# 01_VS1053.net
KiCad netlist of a schematic drawn in Altium Designer
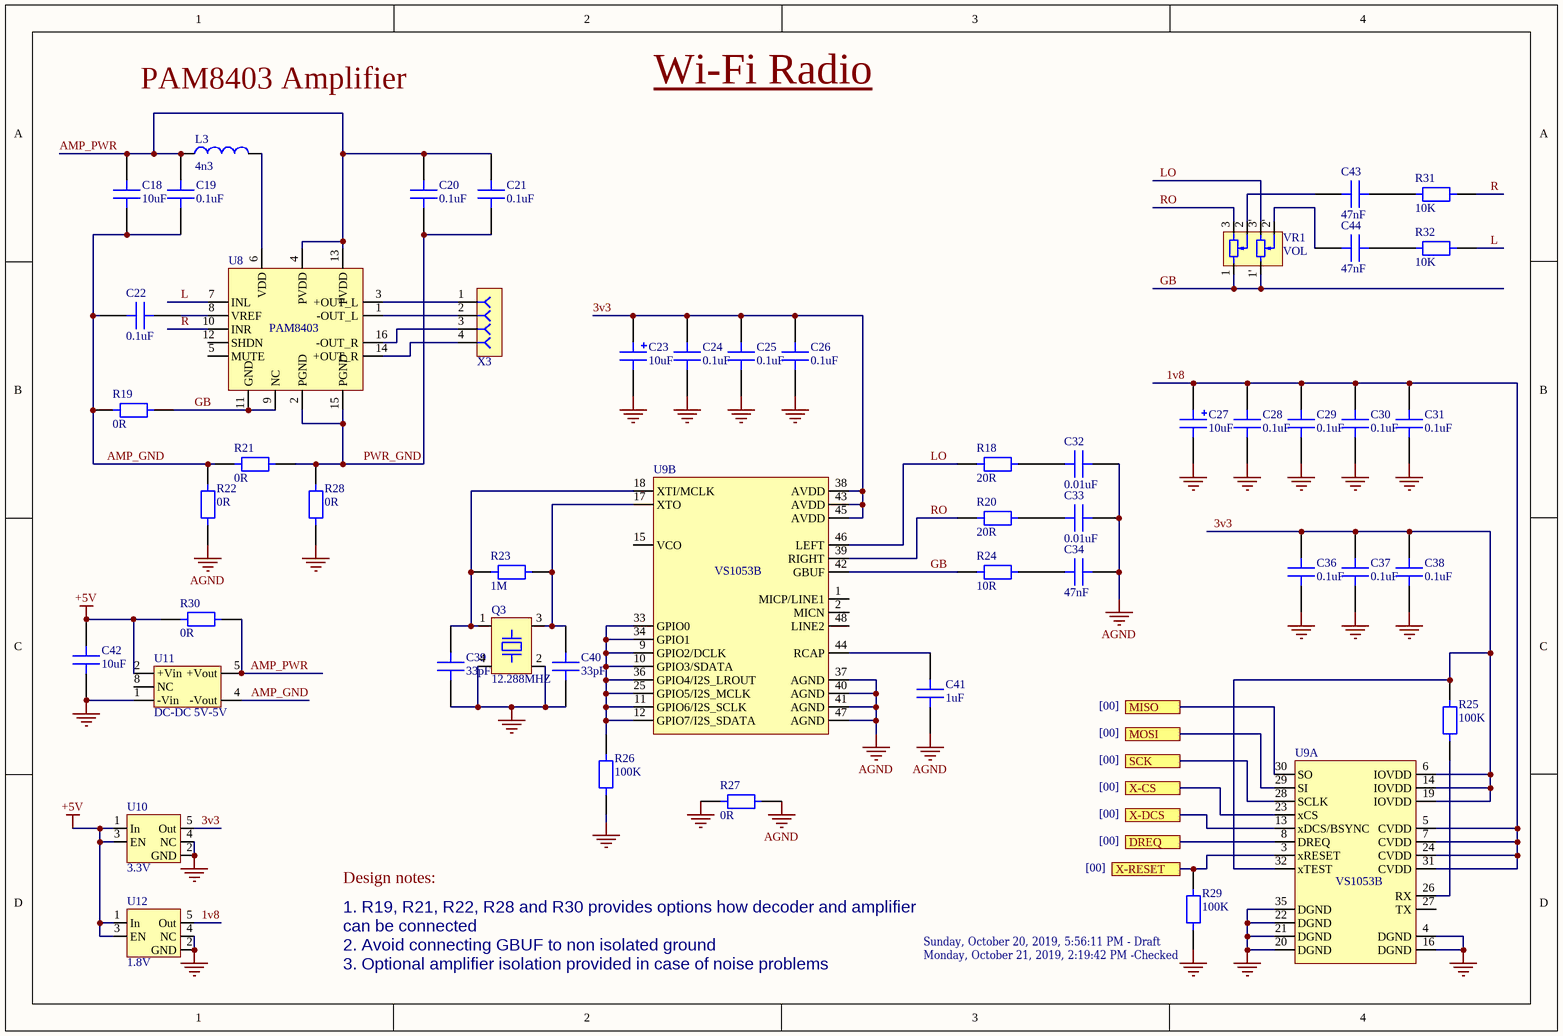
[diagram p0: [01] VS1053.SchDoc]

(export (version "E")
  (design (tool "Eeschema 10.0.6"))
  (components
    (comp (ref "C18")
      (value "10uF")
      (footprint "CAP 0603")
      (description "CAP CER 10UF 0603 6.3V")
      (fields
        (field (name "MANUFACTURER") "KEMET")
        (field (name "MANUFACTURER PART NUMBER") "C0603C106M9PACTU")
      )
      (libsource (lib "WiFi_Lib") (part "C0603C106M9PACTU"))
    )
    (comp (ref "C19")
      (value "0.1uF")
      (footprint "CAP 0603")
      (description "CAP CER 0.1uF 0603- SMD/SMT .1UF 25V 5% 0603")
      (fields
        (field (name "MANUFACTURER") "Vishay Vitramon")
        (field (name "MANUFACTURER PART NUMBER") "VJ0603Y104JXXAC")
      )
      (libsource (lib "WiFi_Lib") (part "VJ0603Y104JXXAC"))
    )
    (comp (ref "C20")
      (value "0.1uF")
      (footprint "CAP 0603")
      (description "CAP CER 0.1uF 0603- SMD/SMT .1UF 25V 5% 0603")
      (fields
        (field (name "MANUFACTURER") "Vishay Vitramon")
        (field (name "MANUFACTURER PART NUMBER") "VJ0603Y104JXXAC")
      )
      (libsource (lib "WiFi_Lib") (part "VJ0603Y104JXXAC"))
    )
    (comp (ref "C21")
      (value "0.1uF")
      (footprint "CAP 0603")
      (description "CAP CER 0.1uF 0603- SMD/SMT .1UF 25V 5% 0603")
      (fields
        (field (name "MANUFACTURER") "Vishay Vitramon")
        (field (name "MANUFACTURER PART NUMBER") "VJ0603Y104JXXAC")
      )
      (libsource (lib "WiFi_Lib") (part "VJ0603Y104JXXAC"))
    )
    (comp (ref "C22")
      (value "0.1uF")
      (footprint "CAP 0603")
      (description "CAP CER 0.1uF 0603- SMD/SMT .1UF 25V 5% 0603")
      (fields
        (field (name "MANUFACTURER") "Vishay Vitramon")
        (field (name "MANUFACTURER PART NUMBER") "VJ0603Y104JXXAC")
      )
      (libsource (lib "WiFi_Lib") (part "VJ0603Y104JXXAC"))
    )
    (comp (ref "C23")
      (value "10uF")
      (footprint "CAP 1206")
      (description "CAP TANT 10UF 1206 6.3V 10%")
      (fields
        (field (name "MANUFACTURER") "Vishay Sprague")
        (field (name "MANUFACTURER PART NUMBER") "293D106X96R3A2TE3")
      )
      (libsource (lib "WiFi_Lib") (part "293D106X96R3A2TE3"))
    )
    (comp (ref "C24")
      (value "0.1uF")
      (footprint "CAP 0603")
      (description "CAP CER 0.1uF 0603- SMD/SMT .1UF 25V 5% 0603")
      (fields
        (field (name "MANUFACTURER") "Vishay Vitramon")
        (field (name "MANUFACTURER PART NUMBER") "VJ0603Y104JXXAC")
      )
      (libsource (lib "WiFi_Lib") (part "VJ0603Y104JXXAC"))
    )
    (comp (ref "C25")
      (value "0.1uF")
      (footprint "CAP 0603")
      (description "CAP CER 0.1uF 0603- SMD/SMT .1UF 25V 5% 0603")
      (fields
        (field (name "MANUFACTURER") "Vishay Vitramon")
        (field (name "MANUFACTURER PART NUMBER") "VJ0603Y104JXXAC")
      )
      (libsource (lib "WiFi_Lib") (part "VJ0603Y104JXXAC"))
    )
    (comp (ref "C26")
      (value "0.1uF")
      (footprint "CAP 0603")
      (description "CAP CER 0.1uF 0603- SMD/SMT .1UF 25V 5% 0603")
      (fields
        (field (name "MANUFACTURER") "Vishay Vitramon")
        (field (name "MANUFACTURER PART NUMBER") "VJ0603Y104JXXAC")
      )
      (libsource (lib "WiFi_Lib") (part "VJ0603Y104JXXAC"))
    )
    (comp (ref "C27")
      (value "10uF")
      (footprint "CAP 1206")
      (description "CAP TANT 10UF 1206 6.3V 10%")
      (fields
        (field (name "MANUFACTURER") "Vishay Sprague")
        (field (name "MANUFACTURER PART NUMBER") "293D106X96R3A2TE3")
      )
      (libsource (lib "WiFi_Lib") (part "293D106X96R3A2TE3"))
    )
    (comp (ref "C28")
      (value "0.1uF")
      (footprint "CAP 0603")
      (description "CAP CER 0.1uF 0603- SMD/SMT .1UF 25V 5% 0603")
      (fields
        (field (name "MANUFACTURER") "Vishay Vitramon")
        (field (name "MANUFACTURER PART NUMBER") "VJ0603Y104JXXAC")
      )
      (libsource (lib "WiFi_Lib") (part "VJ0603Y104JXXAC"))
    )
    (comp (ref "C29")
      (value "0.1uF")
      (footprint "CAP 0603")
      (description "CAP CER 0.1uF 0603- SMD/SMT .1UF 25V 5% 0603")
      (fields
        (field (name "MANUFACTURER") "Vishay Vitramon")
        (field (name "MANUFACTURER PART NUMBER") "VJ0603Y104JXXAC")
      )
      (libsource (lib "WiFi_Lib") (part "VJ0603Y104JXXAC"))
    )
    (comp (ref "C30")
      (value "0.1uF")
      (footprint "CAP 0603")
      (description "CAP CER 0.1uF 0603- SMD/SMT .1UF 25V 5% 0603")
      (fields
        (field (name "MANUFACTURER") "Vishay Vitramon")
        (field (name "MANUFACTURER PART NUMBER") "VJ0603Y104JXXAC")
      )
      (libsource (lib "WiFi_Lib") (part "VJ0603Y104JXXAC"))
    )
    (comp (ref "C31")
      (value "0.1uF")
      (footprint "CAP 0603")
      (description "CAP CER 0.1uF 0603- SMD/SMT .1UF 25V 5% 0603")
      (fields
        (field (name "MANUFACTURER") "Vishay Vitramon")
        (field (name "MANUFACTURER PART NUMBER") "VJ0603Y104JXXAC")
      )
      (libsource (lib "WiFi_Lib") (part "VJ0603Y104JXXAC"))
    )
    (comp (ref "C32")
      (value "0.01uF")
      (footprint "CAP 0603")
      (description "CAP CER 0.01uF 0603 10 nF 50 V ±10 % Tolerance X7R SMT Multilayer Ceramic Chip Capacitor")
      (fields
        (field (name "MANUFACTURER") "Vishay Vitramon")
        (field (name "MANUFACTURER PART NUMBER") "VJ0603Y103KXAAC")
      )
      (libsource (lib "WiFi_Lib") (part "VJ0603Y103KXAAC"))
    )
    (comp (ref "C33")
      (value "0.01uF")
      (footprint "CAP 0603")
      (description "CAP CER 0.01uF 0603 10 nF 50 V ±10 % Tolerance X7R SMT Multilayer Ceramic Chip Capacitor")
      (fields
        (field (name "MANUFACTURER") "Vishay Vitramon")
        (field (name "MANUFACTURER PART NUMBER") "VJ0603Y103KXAAC")
      )
      (libsource (lib "WiFi_Lib") (part "VJ0603Y103KXAAC"))
    )
    (comp (ref "C34")
      (value "47nF")
      (footprint "CAP 0603")
      (description "CAP CER 47nF 0603 25 V ±5 % Tolerance X7R SMT Multilayer Ceramic Chip Capacitor")
      (fields
        (field (name "MANUFACTURER") "Vishay Vitramon")
        (field (name "MANUFACTURER PART NUMBER") "VJ0603Y473JXXCW1BC")
      )
      (libsource (lib "WiFi_Lib") (part "VJ0603Y473JXXCW1BC"))
    )
    (comp (ref "C36")
      (value "0.1uF")
      (footprint "CAP 0603")
      (description "CAP CER 0.1uF 0603- SMD/SMT .1UF 25V 5% 0603")
      (fields
        (field (name "MANUFACTURER") "Vishay Vitramon")
        (field (name "MANUFACTURER PART NUMBER") "VJ0603Y104JXXAC")
      )
      (libsource (lib "WiFi_Lib") (part "VJ0603Y104JXXAC"))
    )
    (comp (ref "C37")
      (value "0.1uF")
      (footprint "CAP 0603")
      (description "CAP CER 0.1uF 0603- SMD/SMT .1UF 25V 5% 0603")
      (fields
        (field (name "MANUFACTURER") "Vishay Vitramon")
        (field (name "MANUFACTURER PART NUMBER") "VJ0603Y104JXXAC")
      )
      (libsource (lib "WiFi_Lib") (part "VJ0603Y104JXXAC"))
    )
    (comp (ref "C38")
      (value "0.1uF")
      (footprint "CAP 0603")
      (description "CAP CER 0.1uF 0603- SMD/SMT .1UF 25V 5% 0603")
      (fields
        (field (name "MANUFACTURER") "Vishay Vitramon")
        (field (name "MANUFACTURER PART NUMBER") "VJ0603Y104JXXAC")
      )
      (libsource (lib "WiFi_Lib") (part "VJ0603Y104JXXAC"))
    )
    (comp (ref "C39")
      (value "33pF")
      (footprint "CAP 0603")
      (description "CAP CER 33PF 0603 250V C0G/NP0")
      (fields
        (field (name "MANUFACTURER") "Johanson")
        (field (name "MANUFACTURER PART NUMBER") "251R14S330GV4T")
      )
      (libsource (lib "WiFi_Lib") (part "251R14S330GV4T"))
    )
    (comp (ref "C40")
      (value "33pF")
      (footprint "CAP 0603")
      (description "CAP CER 33PF 0603 250V C0G/NP0")
      (fields
        (field (name "MANUFACTURER") "Johanson")
        (field (name "MANUFACTURER PART NUMBER") "251R14S330GV4T")
      )
      (libsource (lib "WiFi_Lib") (part "251R14S330GV4T"))
    )
    (comp (ref "C41")
      (value "1uF")
      (footprint "CAP 0603")
      (description "CAP CER 1uF 0603 16V X7R 10% SMD 125C Paper T/R")
      (fields
        (field (name "MANUFACTURER") "Vishay Semiconductors")
        (field (name "MANUFACTURER PART NUMBER") "VJ0603Y105KXJCW1BC")
      )
      (libsource (lib "WiFi_Lib") (part "VJ0603Y105KXJCW1BC"))
    )
    (comp (ref "C42")
      (value "10uF")
      (footprint "CAP 0805")
      (description "CAP CER 10UF 0805 10V X5R")
      (fields
        (field (name "MANUFACTURER") "KEMET")
        (field (name "MANUFACTURER PART NUMBER") "C0805C106K8PACTU")
      )
      (libsource (lib "WiFi_Lib") (part "C0805C106K8PACTU"))
    )
    (comp (ref "C43")
      (value "47nF")
      (footprint "CAP 0603")
      (description "CAP CER 47nF 0603 25 V ±5 % Tolerance X7R SMT Multilayer Ceramic Chip Capacitor")
      (fields
        (field (name "MANUFACTURER") "Vishay Vitramon")
        (field (name "MANUFACTURER PART NUMBER") "VJ0603Y473JXXCW1BC")
      )
      (libsource (lib "WiFi_Lib") (part "VJ0603Y473JXXCW1BC"))
    )
    (comp (ref "C44")
      (value "47nF")
      (footprint "CAP 0603")
      (description "CAP CER 47nF 0603 25 V ±5 % Tolerance X7R SMT Multilayer Ceramic Chip Capacitor")
      (fields
        (field (name "MANUFACTURER") "Vishay Vitramon")
        (field (name "MANUFACTURER PART NUMBER") "VJ0603Y473JXXCW1BC")
      )
      (libsource (lib "WiFi_Lib") (part "VJ0603Y473JXXCW1BC"))
    )
    (comp (ref "L3")
      (value "4n3")
      (footprint "IND 0603 LQW")
      (description "IND SMD 4.3nH 0603 850mA FIXED 59 MOHM")
      (fields
        (field (name "MANUFACTURER") "Murata")
        (field (name "MANUFACTURER PART NUMBER") "LQW18AN4N3D00D")
      )
      (libsource (lib "WiFi_Lib") (part "LQW18AN4N3D00D"))
    )
    (comp (ref "Q3")
      (value "12.288MHZ")
      (footprint "ABM8W")
      (description "CRYSTAL SMD 12.288MHZ Iot Optimized 12.29MHZ 8PF Crystal")
      (fields
        (field (name "MANUFACTURER") "Abracon")
        (field (name "MANUFACTURER PART NUMBER") "ABM8W-12.2880MHZ-8-B1U-T3")
      )
      (libsource (lib "WiFi_Lib") (part "ABM8W-12.2880MHZ-8-B1U-T3"))
    )
    (comp (ref "R18")
      (value "20R")
      (footprint "RES 0603")
      (description "RES SMD 20 0603 1% 1/4W")
      (fields
        (field (name "MANUFACTURER") "Vishay Dale")
        (field (name "MANUFACTURER PART NUMBER") "CRCW060320R0FKEAHP")
      )
      (libsource (lib "WiFi_Lib") (part "CRCW060320R0FKEAHP"))
    )
    (comp (ref "R19")
      (value "0R")
      (footprint "RES 0805 - Jumper")
      (description "RES SMD 0R 0805 JUMPER 1/2W")
      (fields
        (field (name "MANUFACTURER") "Vishay Dale")
        (field (name "MANUFACTURER PART NUMBER") "CRCW08050000Z0EAHP")
      )
      (libsource (lib "WiFi_Lib") (part "CRCW08050000Z0EAHP"))
    )
    (comp (ref "R20")
      (value "20R")
      (footprint "RES 0603")
      (description "RES SMD 20 0603 1% 1/4W")
      (fields
        (field (name "MANUFACTURER") "Vishay Dale")
        (field (name "MANUFACTURER PART NUMBER") "CRCW060320R0FKEAHP")
      )
      (libsource (lib "WiFi_Lib") (part "CRCW060320R0FKEAHP"))
    )
    (comp (ref "R21")
      (value "0R")
      (footprint "RES 0805 - Jumper")
      (description "RES SMD 0R 0805 JUMPER 1/2W")
      (fields
        (field (name "MANUFACTURER") "Vishay Dale")
        (field (name "MANUFACTURER PART NUMBER") "CRCW08050000Z0EAHP")
      )
      (libsource (lib "WiFi_Lib") (part "CRCW08050000Z0EAHP"))
    )
    (comp (ref "R22")
      (value "0R")
      (footprint "RES 0805 - Jumper")
      (description "RES SMD 0R 0805 JUMPER 1/2W")
      (fields
        (field (name "MANUFACTURER") "Vishay Dale")
        (field (name "MANUFACTURER PART NUMBER") "CRCW08050000Z0EAHP")
      )
      (libsource (lib "WiFi_Lib") (part "CRCW08050000Z0EAHP"))
    )
    (comp (ref "R23")
      (value "1M")
      (footprint "RES 0603")
      (description "RES SMD 1M 0603 1% 1/10W")
      (fields
        (field (name "MANUFACTURER") "Vishay")
        (field (name "MANUFACTURER PART NUMBER") "CRCW06031M00FKEA")
      )
      (libsource (lib "WiFi_Lib") (part "CRCW06031M00FKEA"))
    )
    (comp (ref "R24")
      (value "10R")
      (footprint "RES 0603")
      (description "RES SMD 10 0603 1% 1/4W")
      (fields
        (field (name "MANUFACTURER") "Vishay Dale")
        (field (name "MANUFACTURER PART NUMBER") "RCA060310R0FKEAHP")
      )
      (libsource (lib "WiFi_Lib") (part "RCA060310R0FKEAHP"))
    )
    (comp (ref "R25")
      (value "100K")
      (footprint "RES 0603")
      (description "RES SMD 100K 0603 0.1W 1% SMT TCR 37 ppm/DegC")
      (fields
        (field (name "MANUFACTURER") "Vishay")
        (field (name "MANUFACTURER PART NUMBER") "CRCW0603-100KFKEA")
      )
      (libsource (lib "WiFi_Lib") (part "CRCW0603-100KFKEA"))
    )
    (comp (ref "R26")
      (value "100K")
      (footprint "RES 0603")
      (description "RES SMD 100K 0603 0.1W 1% SMT TCR 37 ppm/DegC")
      (fields
        (field (name "MANUFACTURER") "Vishay")
        (field (name "MANUFACTURER PART NUMBER") "CRCW0603-100KFKEA")
      )
      (libsource (lib "WiFi_Lib") (part "CRCW0603-100KFKEA"))
    )
    (comp (ref "R27")
      (value "0R")
      (footprint "RES 0603 - Jumper")
      (description "RES SMD 0R 0603 JUMPER PU=5000 ST, CRCW06030000Z0EA, Vishay")
      (fields
        (field (name "MANUFACTURER") "Vishay")
        (field (name "MANUFACTURER PART NUMBER") "CRCW0603-0000Z0EA")
      )
      (libsource (lib "WiFi_Lib") (part "CRCW0603-0000Z0EA"))
    )
    (comp (ref "R28")
      (value "0R")
      (footprint "RES 0805 - Jumper")
      (description "RES SMD 0R 0805 JUMPER 1/2W")
      (fields
        (field (name "MANUFACTURER") "Vishay Dale")
        (field (name "MANUFACTURER PART NUMBER") "CRCW08050000Z0EAHP")
      )
      (libsource (lib "WiFi_Lib") (part "CRCW08050000Z0EAHP"))
    )
    (comp (ref "R29")
      (value "100K")
      (footprint "RES 0603")
      (description "RES SMD 100K 0603 0.1W 1% SMT TCR 37 ppm/DegC")
      (fields
        (field (name "MANUFACTURER") "Vishay")
        (field (name "MANUFACTURER PART NUMBER") "CRCW0603-100KFKEA")
      )
      (libsource (lib "WiFi_Lib") (part "CRCW0603-100KFKEA"))
    )
    (comp (ref "R30")
      (value "0R")
      (footprint "RES 0805 - Jumper")
      (description "RES SMD 0R 0805 JUMPER 1/2W")
      (fields
        (field (name "MANUFACTURER") "Vishay Dale")
        (field (name "MANUFACTURER PART NUMBER") "CRCW08050000Z0EAHP")
      )
      (libsource (lib "WiFi_Lib") (part "CRCW08050000Z0EAHP"))
    )
    (comp (ref "R31")
      (value "10K")
      (footprint "RES 0603")
      (description "RES SMD 10K 0603 1% 1/10W")
      (fields
        (field (name "MANUFACTURER") "Vishay")
        (field (name "MANUFACTURER PART NUMBER") "CRCW060310K0FKEA")
      )
      (libsource (lib "WiFi_Lib") (part "CRCW060310K0FKEA"))
    )
    (comp (ref "R32")
      (value "10K")
      (footprint "RES 0603")
      (description "RES SMD 10K 0603 1% 1/10W")
      (fields
        (field (name "MANUFACTURER") "Vishay")
        (field (name "MANUFACTURER PART NUMBER") "CRCW060310K0FKEA")
      )
      (libsource (lib "WiFi_Lib") (part "CRCW060310K0FKEA"))
    )
    (comp (ref "U8")
      (value "PAM8403")
      (footprint "SOP-16")
      (description "IC AMP AUDIO 3W CLASS D 16SOIC")
      (fields (field (name "MANUFACTURER") "Diodes") (field (name "MANUFACTURER PART NUMBER") "PAM8403DR-H"))
      (libsource (lib "WiFi_Lib") (part "PAM8403DR-H"))
    )
    (comp (ref "U9")
      (value "VS1053B")
      (footprint "LQFP-48")
      (description "IC VS1053B MP3/WAV/OGG/MIDI Player & Recorder (CODEC) Chip")
      (fields
        (field (name "MANUFACTURER") "Adafruit Industries")
        (field (name "MANUFACTURER PART NUMBER") "1681")
      )
      (libsource (lib "WiFi_Lib") (part "1681"))
    )
    (comp (ref "U10")
      (value "3.3V")
      (footprint "SOT-23-5")
      (description "IC REG LIN 3.3V 300mALow IQLDO Reg")
      (fields
        (field (name "MANUFACTURER") "Texas Instruments")
        (field (name "MANUFACTURER PART NUMBER") "TLV70233DBVR")
      )
      (libsource (lib "WiFi_Lib") (part "TLV70233DBVR"))
    )
    (comp (ref "U11")
      (value "DC-DC 5V-5V")
      (footprint "R1SE DC/DC")
      (description "DC DC CONVERTER 5V 1W")
      (fields (field (name "MANUFACTURER") "Recom") (field (name "MANUFACTURER PART NUMBER") "R1SE-0505-R"))
      (libsource (lib "WiFi_Lib") (part "R1SE-0505-R"))
    )
    (comp (ref "U12")
      (value "1.8V")
      (footprint "SOT-23-5")
      (description "IC REG LIN 1.8V 300MA SOT23-5")
      (fields
        (field (name "MANUFACTURER") "Texas Instruments")
        (field (name "MANUFACTURER PART NUMBER") "TLV70218DBVT")
      )
      (libsource (lib "WiFi_Lib") (part "TLV70218DBVT"))
    )
    (comp (ref "VR1")
      (value "VOL")
      (footprint "POT PTD902")
      (description "POT 50K LINEAR")
      (fields
        (field (name "MANUFACTURER") "Bourns")
        (field (name "MANUFACTURER PART NUMBER") "PTD902-1025K-B503")
      )
      (libsource (lib "WiFi_Lib") (part "PTD902-1025K-B503"))
    )
    (comp (ref "X3")
      (value "0393570004")
      (footprint "TRMINAL 3.5MM")
      (description "TERMINAL 4 POS 3.5mm Solder ST Thru-Hole 17.5A/Contact Eurostyle™")
      (fields (field (name "MANUFACTURER") "Molex") (field (name "VOLTAGE") "300V"))
      (libsource (lib "WiFi_Lib") (part "0393570004"))
    )
  )
  (nets
    (net (code "1") (name "+5V") (class "Default")
      (node (ref "C42") (pin "2") (pinfunction "2_2") (pintype "passive"))
      (node (ref "R30") (pin "1") (pinfunction "1_1") (pintype "passive"))
      (node (ref "U10") (pin "1") (pinfunction "In_1") (pintype "passive"))
      (node (ref "U10") (pin "3") (pinfunction "EN_3") (pintype "passive"))
      (node (ref "U11") (pin "2") (pinfunction "+Vin_2") (pintype "passive"))
      (node (ref "U12") (pin "1") (pinfunction "In_1") (pintype "passive"))
      (node (ref "U12") (pin "3") (pinfunction "EN_3") (pintype "passive"))
    )
    (net (code "2") (name "/1v8") (class "Default")
      (node (ref "C27") (pin "1") (pinfunction "1_1") (pintype "passive"))
      (node (ref "C28") (pin "2") (pinfunction "2_2") (pintype "passive"))
      (node (ref "C29") (pin "2") (pinfunction "2_2") (pintype "passive"))
      (node (ref "C30") (pin "2") (pinfunction "2_2") (pintype "passive"))
      (node (ref "C31") (pin "2") (pinfunction "2_2") (pintype "passive"))
      (node (ref "U12") (pin "5") (pinfunction "Out_5") (pintype "passive"))
      (node (ref "U9") (pin "24") (pinfunction "CVDD_24") (pintype "passive"))
      (node (ref "U9") (pin "31") (pinfunction "CVDD_31") (pintype "passive"))
      (node (ref "U9") (pin "5") (pinfunction "CVDD_5") (pintype "passive"))
      (node (ref "U9") (pin "7") (pinfunction "CVDD_7") (pintype "passive"))
    )
    (net (code "3") (name "/3v3") (class "Default")
      (node (ref "C23") (pin "1") (pinfunction "1_1") (pintype "passive"))
      (node (ref "C24") (pin "2") (pinfunction "2_2") (pintype "passive"))
      (node (ref "C25") (pin "2") (pinfunction "2_2") (pintype "passive"))
      (node (ref "C26") (pin "2") (pinfunction "2_2") (pintype "passive"))
      (node (ref "C36") (pin "2") (pinfunction "2_2") (pintype "passive"))
      (node (ref "C37") (pin "2") (pinfunction "2_2") (pintype "passive"))
      (node (ref "C38") (pin "2") (pinfunction "2_2") (pintype "passive"))
      (node (ref "R25") (pin "1") (pinfunction "1_1") (pintype "passive"))
      (node (ref "U10") (pin "5") (pinfunction "Out_5") (pintype "passive"))
      (node (ref "U9") (pin "14") (pinfunction "IOVDD_14") (pintype "passive"))
      (node (ref "U9") (pin "19") (pinfunction "IOVDD_19") (pintype "passive"))
      (node (ref "U9") (pin "32") (pinfunction "xTEST_32") (pintype "passive"))
      (node (ref "U9") (pin "38") (pinfunction "AVDD_38") (pintype "passive"))
      (node (ref "U9") (pin "43") (pinfunction "AVDD_43") (pintype "passive"))
      (node (ref "U9") (pin "45") (pinfunction "AVDD_45") (pintype "passive"))
      (node (ref "U9") (pin "6") (pinfunction "IOVDD_6") (pintype "passive"))
    )
    (net (code "4") (name "/AMP_GND") (class "Default")
      (node (ref "C18") (pin "1") (pinfunction "1_1") (pintype "passive"))
      (node (ref "C19") (pin "1") (pinfunction "1_1") (pintype "passive"))
      (node (ref "C22") (pin "2") (pinfunction "2_2") (pintype "passive"))
      (node (ref "R19") (pin "2") (pinfunction "2_2") (pintype "passive"))
      (node (ref "R21") (pin "1") (pinfunction "1_1") (pintype "passive"))
      (node (ref "R22") (pin "2") (pinfunction "2_2") (pintype "passive"))
      (node (ref "U11") (pin "4") (pinfunction "-Vout_4") (pintype "passive"))
    )
    (net (code "5") (name "/AMP_PWR") (class "Default")
      (node (ref "C18") (pin "2") (pinfunction "2_2") (pintype "passive"))
      (node (ref "C19") (pin "2") (pinfunction "2_2") (pintype "passive"))
      (node (ref "C20") (pin "2") (pinfunction "2_2") (pintype "passive"))
      (node (ref "C21") (pin "2") (pinfunction "2_2") (pintype "passive"))
      (node (ref "L3") (pin "1") (pinfunction "1_1") (pintype "passive"))
      (node (ref "R30") (pin "2") (pinfunction "2_2") (pintype "passive"))
      (node (ref "U11") (pin "5") (pinfunction "+Vout_5") (pintype "passive"))
      (node (ref "U8") (pin "13") (pinfunction "PVDD_13") (pintype "passive"))
      (node (ref "U8") (pin "4") (pinfunction "PVDD_4") (pintype "passive"))
    )
    (net (code "6") (name "/DREQ") (class "Default")
      (node (ref "U9") (pin "8") (pinfunction "DREQ_8") (pintype "passive"))
    )
    (net (code "7") (name "/GB") (class "Default")
      (node (ref "R19") (pin "1") (pinfunction "1_1") (pintype "passive"))
      (node (ref "R24") (pin "1") (pinfunction "1_1") (pintype "passive"))
      (node (ref "U8") (pin "11") (pinfunction "GND_11") (pintype "passive"))
      (node (ref "U8") (pin "9") (pinfunction "NC_9") (pintype "passive"))
      (node (ref "U9") (pin "42") (pinfunction "GBUF_42") (pintype "passive"))
      (node (ref "VR1") (pin "1") (pinfunction "1_1") (pintype "passive"))
      (node (ref "VR1") (pin "1'") (pinfunction "1'_1'") (pintype "passive"))
    )
    (net (code "8") (name "/L") (class "Default")
      (node (ref "R32") (pin "2") (pinfunction "2_2") (pintype "passive"))
      (node (ref "U8") (pin "7") (pinfunction "INL_7") (pintype "passive"))
    )
    (net (code "9") (name "/LO") (class "Default")
      (node (ref "R18") (pin "1") (pinfunction "1_1") (pintype "passive"))
      (node (ref "U9") (pin "46") (pinfunction "LEFT_46") (pintype "passive"))
      (node (ref "VR1") (pin "3'") (pinfunction "3'_3'") (pintype "passive"))
    )
    (net (code "10") (name "/MISO") (class "Default")
      (node (ref "U9") (pin "30") (pinfunction "SO_30") (pintype "passive"))
    )
    (net (code "11") (name "/MOSI") (class "Default")
      (node (ref "U9") (pin "29") (pinfunction "SI_29") (pintype "passive"))
    )
    (net (code "12") (name "/PWR_GND") (class "Default")
      (node (ref "C20") (pin "1") (pinfunction "1_1") (pintype "passive"))
      (node (ref "C21") (pin "1") (pinfunction "1_1") (pintype "passive"))
      (node (ref "R21") (pin "2") (pinfunction "2_2") (pintype "passive"))
      (node (ref "R28") (pin "2") (pinfunction "2_2") (pintype "passive"))
      (node (ref "U8") (pin "15") (pinfunction "PGND_15") (pintype "passive"))
      (node (ref "U8") (pin "2") (pinfunction "PGND_2") (pintype "passive"))
    )
    (net (code "13") (name "/R") (class "Default")
      (node (ref "R31") (pin "2") (pinfunction "2_2") (pintype "passive"))
      (node (ref "U8") (pin "10") (pinfunction "INR_10") (pintype "passive"))
    )
    (net (code "14") (name "/RO") (class "Default")
      (node (ref "R20") (pin "1") (pinfunction "1_1") (pintype "passive"))
      (node (ref "U9") (pin "39") (pinfunction "RIGHT_39") (pintype "passive"))
      (node (ref "VR1") (pin "3") (pinfunction "3_3") (pintype "passive"))
    )
    (net (code "15") (name "/SCK") (class "Default")
      (node (ref "U9") (pin "28") (pinfunction "SCLK_28") (pintype "passive"))
    )
    (net (code "16") (name "/X-CS") (class "Default")
      (node (ref "U9") (pin "23") (pinfunction "xCS_23") (pintype "passive"))
    )
    (net (code "17") (name "/X-DCS") (class "Default")
      (node (ref "U9") (pin "13") (pinfunction "xDCS/BSYNC_13") (pintype "passive"))
    )
    (net (code "18") (name "/X-RESET") (class "Default")
      (node (ref "R29") (pin "2") (pinfunction "2_2") (pintype "passive"))
      (node (ref "U9") (pin "3") (pinfunction "xRESET_3") (pintype "passive"))
    )
    (net (code "19") (name "AGND") (class "Default")
      (node (ref "C32") (pin "2") (pinfunction "2_2") (pintype "passive"))
      (node (ref "C33") (pin "2") (pinfunction "2_2") (pintype "passive"))
      (node (ref "C34") (pin "2") (pinfunction "2_2") (pintype "passive"))
      (node (ref "C41") (pin "1") (pinfunction "1_1") (pintype "passive"))
      (node (ref "R22") (pin "1") (pinfunction "1_1") (pintype "passive"))
      (node (ref "R27") (pin "2") (pinfunction "2_2") (pintype "passive"))
      (node (ref "U9") (pin "37") (pinfunction "AGND_37") (pintype "passive"))
      (node (ref "U9") (pin "40") (pinfunction "AGND_40") (pintype "passive"))
      (node (ref "U9") (pin "41") (pinfunction "AGND_41") (pintype "passive"))
      (node (ref "U9") (pin "47") (pinfunction "AGND_47") (pintype "passive"))
    )
    (net (code "20") (name "GND") (class "Default")
      (node (ref "C23") (pin "2") (pinfunction "2_2") (pintype "passive"))
      (node (ref "C24") (pin "1") (pinfunction "1_1") (pintype "passive"))
      (node (ref "C25") (pin "1") (pinfunction "1_1") (pintype "passive"))
      (node (ref "C26") (pin "1") (pinfunction "1_1") (pintype "passive"))
      (node (ref "C27") (pin "2") (pinfunction "2_2") (pintype "passive"))
      (node (ref "C28") (pin "1") (pinfunction "1_1") (pintype "passive"))
      (node (ref "C29") (pin "1") (pinfunction "1_1") (pintype "passive"))
      (node (ref "C30") (pin "1") (pinfunction "1_1") (pintype "passive"))
      (node (ref "C31") (pin "1") (pinfunction "1_1") (pintype "passive"))
      (node (ref "C36") (pin "1") (pinfunction "1_1") (pintype "passive"))
      (node (ref "C37") (pin "1") (pinfunction "1_1") (pintype "passive"))
      (node (ref "C38") (pin "1") (pinfunction "1_1") (pintype "passive"))
      (node (ref "C39") (pin "1") (pinfunction "1_1") (pintype "passive"))
      (node (ref "C40") (pin "1") (pinfunction "1_1") (pintype "passive"))
      (node (ref "C42") (pin "1") (pinfunction "1_1") (pintype "passive"))
      (node (ref "Q3") (pin "2") (pinfunction "GND_2") (pintype "passive"))
      (node (ref "Q3") (pin "4") (pinfunction "GND_4") (pintype "passive"))
      (node (ref "R26") (pin "1") (pinfunction "1_1") (pintype "passive"))
      (node (ref "R27") (pin "1") (pinfunction "1_1") (pintype "passive"))
      (node (ref "R28") (pin "1") (pinfunction "1_1") (pintype "passive"))
      (node (ref "R29") (pin "1") (pinfunction "1_1") (pintype "passive"))
      (node (ref "U10") (pin "2") (pinfunction "GND_2") (pintype "passive"))
      (node (ref "U10") (pin "4") (pinfunction "NC_4") (pintype "passive"))
      (node (ref "U11") (pin "1") (pinfunction "-Vin_1") (pintype "passive"))
      (node (ref "U12") (pin "2") (pinfunction "GND_2") (pintype "passive"))
      (node (ref "U12") (pin "4") (pinfunction "NC_4") (pintype "passive"))
      (node (ref "U9") (pin "16") (pinfunction "DGND_16") (pintype "passive"))
      (node (ref "U9") (pin "20") (pinfunction "DGND_20") (pintype "passive"))
      (node (ref "U9") (pin "21") (pinfunction "DGND_21") (pintype "passive"))
      (node (ref "U9") (pin "22") (pinfunction "DGND_22") (pintype "passive"))
      (node (ref "U9") (pin "35") (pinfunction "DGND_35") (pintype "passive"))
      (node (ref "U9") (pin "4") (pinfunction "DGND_4") (pintype "passive"))
    )
    (net (code "21") (name "Net-(C32-Pad1)") (class "Default")
      (node (ref "C32") (pin "1") (pinfunction "1_1") (pintype "passive"))
      (node (ref "R18") (pin "2") (pinfunction "2_2") (pintype "passive"))
    )
    (net (code "22") (name "Net-(C33-Pad1)") (class "Default")
      (node (ref "C33") (pin "1") (pinfunction "1_1") (pintype "passive"))
      (node (ref "R20") (pin "2") (pinfunction "2_2") (pintype "passive"))
    )
    (net (code "23") (name "Net-(C34-Pad1)") (class "Default")
      (node (ref "C34") (pin "1") (pinfunction "1_1") (pintype "passive"))
      (node (ref "R24") (pin "2") (pinfunction "2_2") (pintype "passive"))
    )
    (net (code "24") (name "Net-(C43-Pad1)") (class "Default")
      (node (ref "C43") (pin "1") (pinfunction "1_1") (pintype "passive"))
      (node (ref "VR1") (pin "2") (pinfunction "2_2") (pintype "passive"))
    )
    (net (code "25") (name "Net-(C43-Pad2)") (class "Default")
      (node (ref "C43") (pin "2") (pinfunction "2_2") (pintype "passive"))
      (node (ref "R31") (pin "1") (pinfunction "1_1") (pintype "passive"))
    )
    (net (code "26") (name "Net-(C44-Pad1)") (class "Default")
      (node (ref "C44") (pin "1") (pinfunction "1_1") (pintype "passive"))
      (node (ref "VR1") (pin "2'") (pinfunction "2'_2'") (pintype "passive"))
    )
    (net (code "27") (name "Net-(C44-Pad2)") (class "Default")
      (node (ref "C44") (pin "2") (pinfunction "2_2") (pintype "passive"))
      (node (ref "R32") (pin "1") (pinfunction "1_1") (pintype "passive"))
    )
    (net (code "28") (name "Net-(U8-+OUT_L)") (class "Default")
      (node (ref "U8") (pin "3") (pinfunction "+OUT_L_3") (pintype "passive"))
      (node (ref "X3") (pin "1") (pinfunction "1_1") (pintype "passive"))
    )
    (net (code "29") (name "Net-(U8-+OUT_R)") (class "Default")
      (node (ref "U8") (pin "14") (pinfunction "+OUT_R_14") (pintype "passive"))
      (node (ref "X3") (pin "4") (pinfunction "4_4") (pintype "passive"))
    )
    (net (code "30") (name "Net-(U8--OUT_L)") (class "Default")
      (node (ref "U8") (pin "1") (pinfunction "-OUT_L_1") (pintype "passive"))
      (node (ref "X3") (pin "2") (pinfunction "2_2") (pintype "passive"))
    )
    (net (code "31") (name "Net-(U8--OUT_R)") (class "Default")
      (node (ref "U8") (pin "16") (pinfunction "-OUT_R_16") (pintype "passive"))
      (node (ref "X3") (pin "3") (pinfunction "3_3") (pintype "passive"))
    )
    (net (code "32") (name "Net-(U8-VDD)") (class "Default")
      (node (ref "L3") (pin "2") (pinfunction "2_2") (pintype "passive"))
      (node (ref "U8") (pin "6") (pinfunction "VDD_6") (pintype "passive"))
    )
    (net (code "33") (name "Net-(U8-VREF)") (class "Default")
      (node (ref "C22") (pin "1") (pinfunction "1_1") (pintype "passive"))
      (node (ref "U8") (pin "8") (pinfunction "VREF_8") (pintype "passive"))
    )
    (net (code "34") (name "Net-(U9A-RX)") (class "Default")
      (node (ref "R25") (pin "2") (pinfunction "2_2") (pintype "passive"))
      (node (ref "U9") (pin "26") (pinfunction "RX_26") (pintype "passive"))
    )
    (net (code "35") (name "Net-(U9B-GPIO0)") (class "Default")
      (node (ref "R26") (pin "2") (pinfunction "2_2") (pintype "passive"))
      (node (ref "U9") (pin "10") (pinfunction "GPIO3/SDATA_10") (pintype "passive"))
      (node (ref "U9") (pin "11") (pinfunction "GPIO6/I2S_SCLK_11") (pintype "passive"))
      (node (ref "U9") (pin "12") (pinfunction "GPIO7/I2S_SDATA_12") (pintype "passive"))
      (node (ref "U9") (pin "25") (pinfunction "GPIO5/I2S_MCLK_25") (pintype "passive"))
      (node (ref "U9") (pin "33") (pinfunction "GPIO0_33") (pintype "passive"))
      (node (ref "U9") (pin "34") (pinfunction "GPIO1_34") (pintype "passive"))
      (node (ref "U9") (pin "36") (pinfunction "GPIO4/I2S_LROUT_36") (pintype "passive"))
      (node (ref "U9") (pin "9") (pinfunction "GPIO2/DCLK_9") (pintype "passive"))
    )
    (net (code "36") (name "Net-(U9B-RCAP)") (class "Default")
      (node (ref "C41") (pin "2") (pinfunction "2_2") (pintype "passive"))
      (node (ref "U9") (pin "44") (pinfunction "RCAP_44") (pintype "passive"))
    )
    (net (code "37") (name "Net-(U9B-XTI{slash}MCLK)") (class "Default")
      (node (ref "C39") (pin "2") (pinfunction "2_2") (pintype "passive"))
      (node (ref "Q3") (pin "1") (pinfunction "1_1") (pintype "passive"))
      (node (ref "R23") (pin "1") (pinfunction "1_1") (pintype "passive"))
      (node (ref "U9") (pin "18") (pinfunction "XTI/MCLK_18") (pintype "passive"))
    )
    (net (code "38") (name "Net-(U9B-XTO)") (class "Default")
      (node (ref "C40") (pin "2") (pinfunction "2_2") (pintype "passive"))
      (node (ref "Q3") (pin "3") (pinfunction "3_3") (pintype "passive"))
      (node (ref "R23") (pin "2") (pinfunction "2_2") (pintype "passive"))
      (node (ref "U9") (pin "17") (pinfunction "XTO_17") (pintype "passive"))
    )
    (net (code "39") (name "unconnected-(U8-MUTE-Pad5)") (class "Default")
      (node (ref "U8") (pin "5") (pinfunction "MUTE_5") (pintype "passive"))
    )
    (net (code "40") (name "unconnected-(U8-SHDN-Pad12)") (class "Default")
      (node (ref "U8") (pin "12") (pinfunction "SHDN_12") (pintype "passive"))
    )
    (net (code "41") (name "unconnected-(U9A-TX-Pad27)") (class "Default")
      (node (ref "U9") (pin "27") (pinfunction "TX_27") (pintype "passive"))
    )
    (net (code "42") (name "unconnected-(U9B-LINE2-Pad48)") (class "Default")
      (node (ref "U9") (pin "48") (pinfunction "LINE2_48") (pintype "passive"))
    )
    (net (code "43") (name "unconnected-(U9B-MICN-Pad2)") (class "Default")
      (node (ref "U9") (pin "2") (pinfunction "MICN_2") (pintype "passive"))
    )
    (net (code "44") (name "unconnected-(U9B-MICP{slash}LINE1-Pad1)") (class "Default")
      (node (ref "U9") (pin "1") (pinfunction "MICP/LINE1_1") (pintype "passive"))
    )
    (net (code "45") (name "unconnected-(U9B-VCO-Pad15)") (class "Default")
      (node (ref "U9") (pin "15") (pinfunction "VCO_15") (pintype "passive"))
    )
    (net (code "46") (name "unconnected-(U11-NC-Pad8)") (class "Default")
      (node (ref "U11") (pin "8") (pinfunction "NC_8") (pintype "passive"))
    )
  )
)
